# SCH_business-card_2024-06-18.net
KiCad netlist of a schematic drawn in EasyEDA
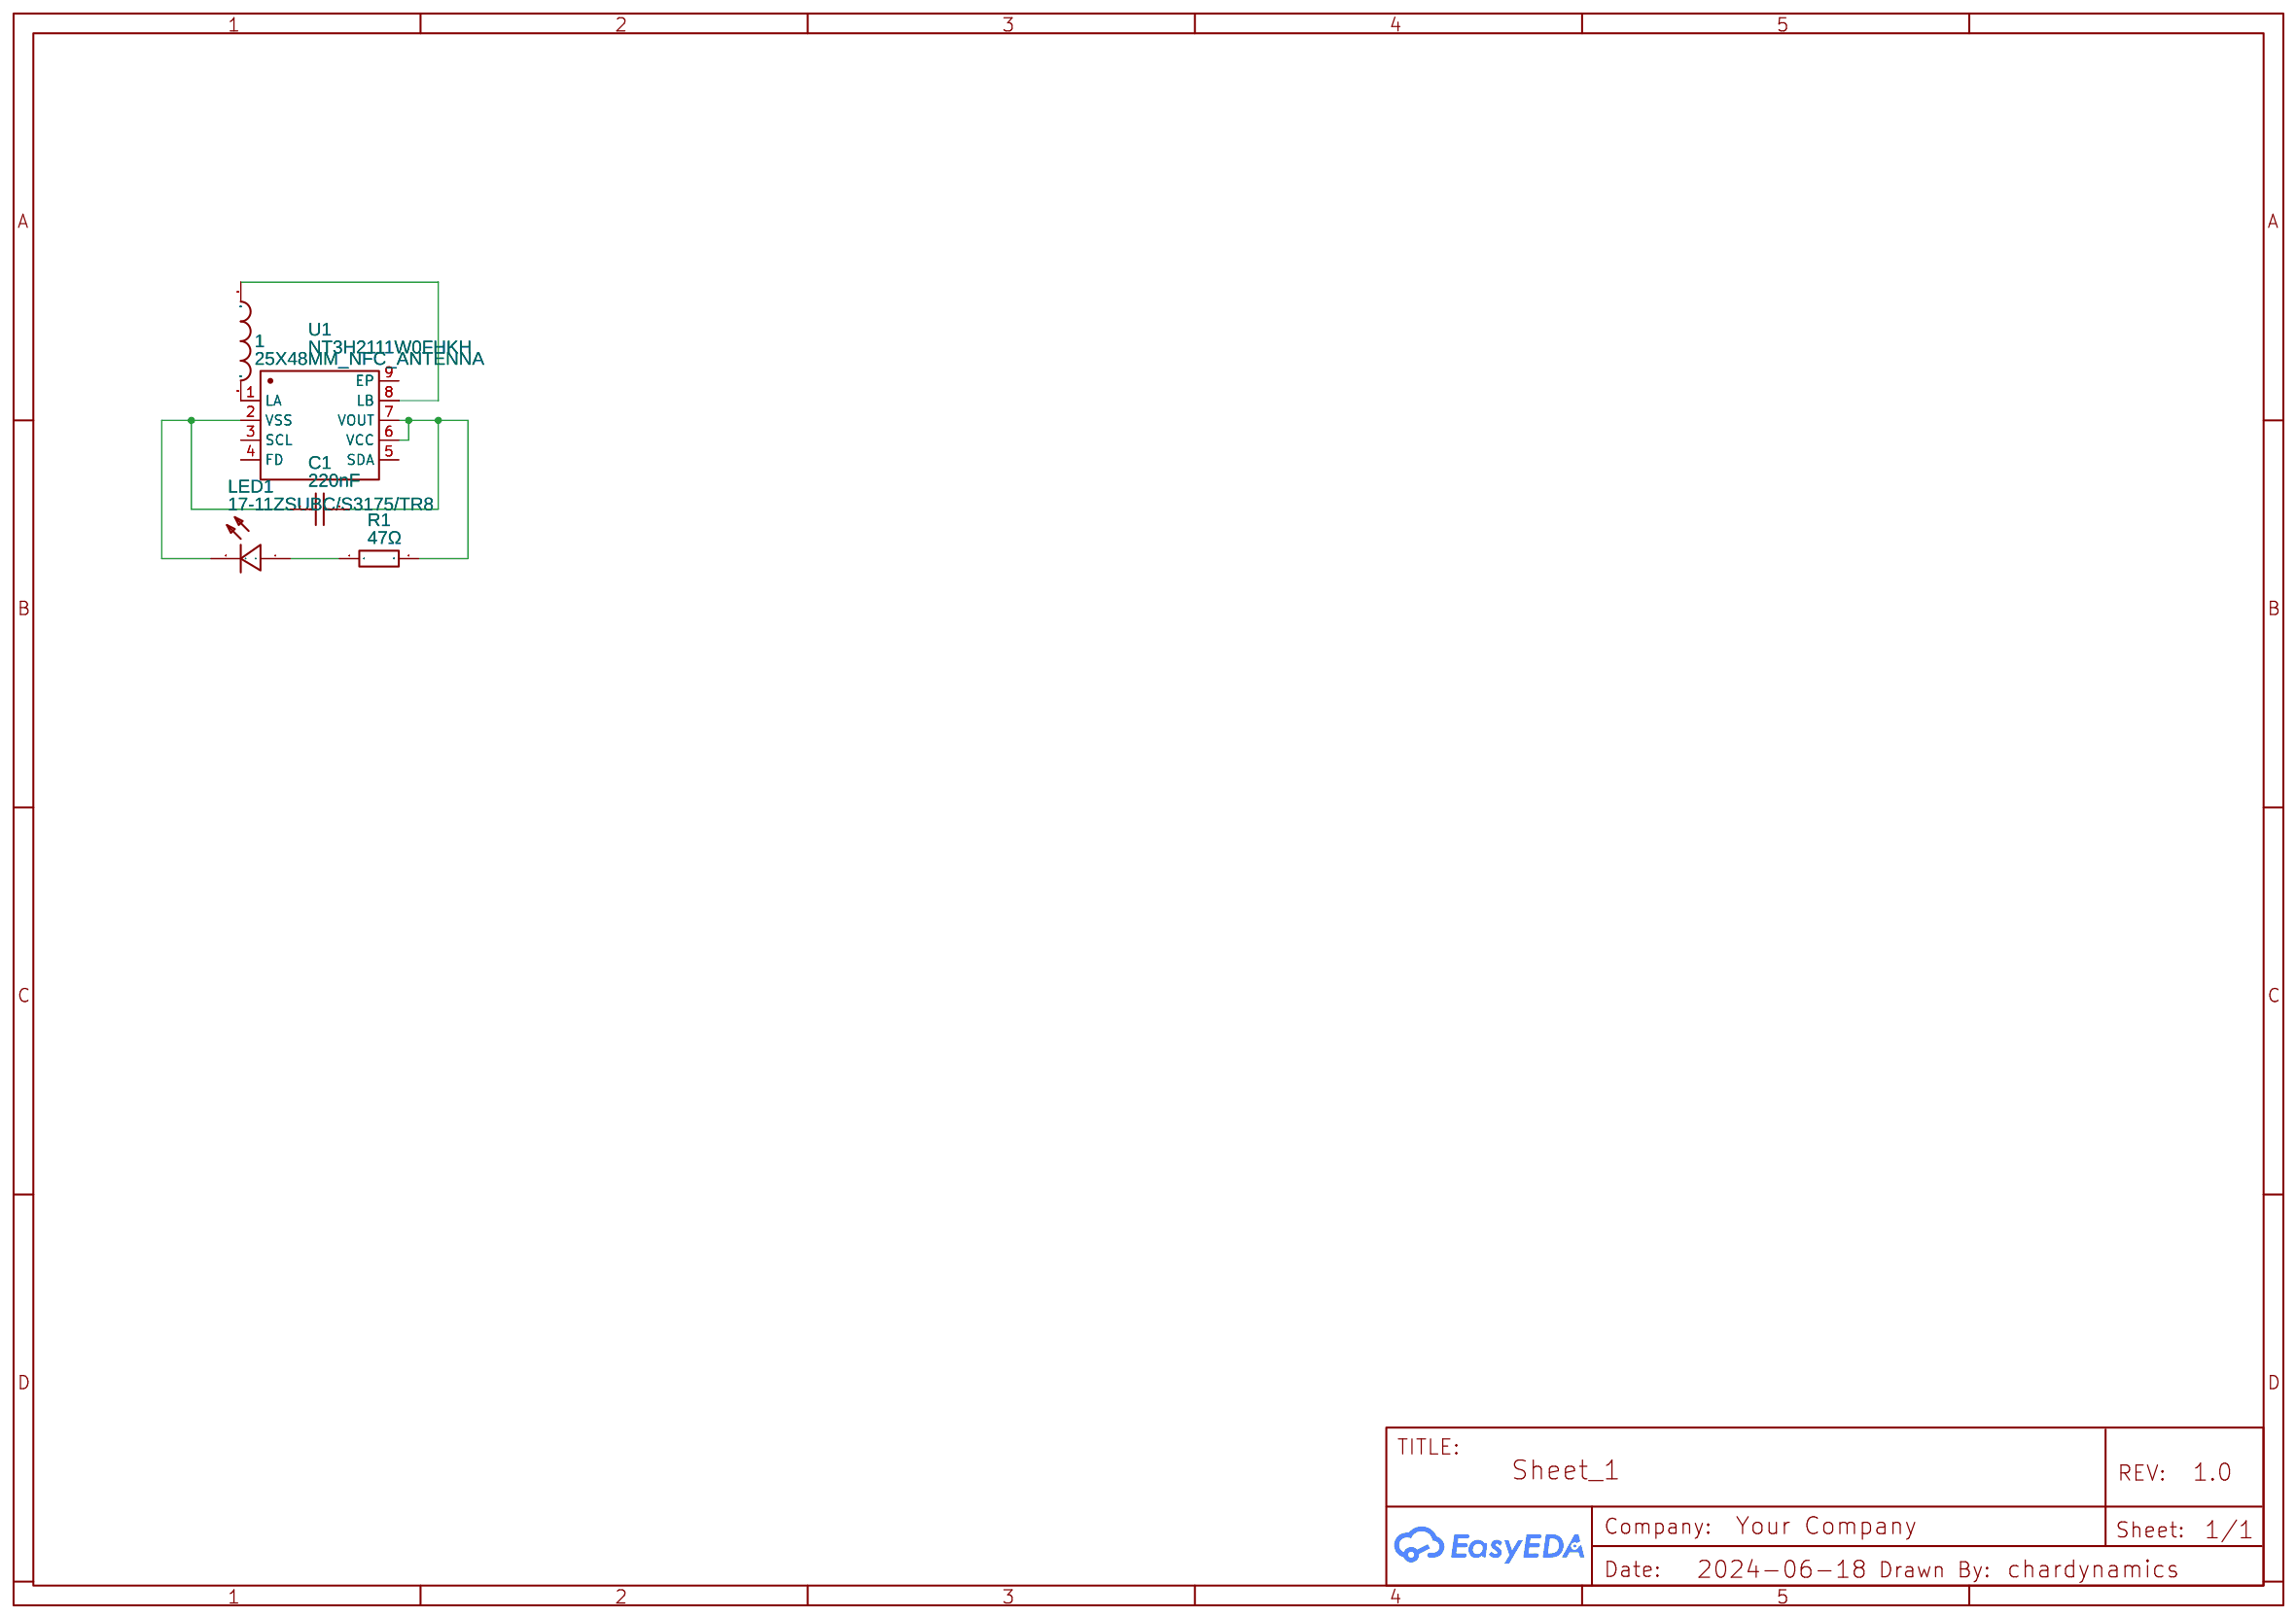
[diagram p0: schematic sheet]

(export (version "E")
  (design (tool "Eeschema 10.0.6"))
  (components
    (comp (ref "1") (value "25X48MM_NFC_ANTENNA") (libsource (lib "") (part "25X48MM_NFC_ANTENNA")))
    (comp (ref "C1")
      (value "220nF")
      (fields
        (field (name "Manufacturer Part") "CL10B224KA8NNNC")
        (field (name "Manufacturer") "SAMSUNG(三星)")
      )
      (libsource (lib "") (part "CL10B224KA8NNNC"))
    )
    (comp (ref "LED1")
      (value "17-11ZSUBC/S3175/TR8")
      (fields (field (name "Manufacturer") "EVERLIGHT(亿光)"))
      (libsource (lib "") (part "17-11ZSUBC/S3175/TR8"))
    )
    (comp (ref "R1")
      (value "47Ω")
      (fields
        (field (name "Manufacturer Part") "0603WAF470JT5E")
        (field (name "Manufacturer") "UNI-ROYAL(厚声)")
      )
      (libsource (lib "") (part "0603WAF470JT5E"))
    )
    (comp (ref "U1")
      (value "NT3H2111W0FHKH")
      (fields (field (name "Manufacturer") "NXP(恩智浦)"))
      (libsource (lib "") (part "NT3H2111W0FHKH"))
    )
  )
  (nets
    (net (code "1") (name "Net-(LED1-A)") (class "Default")
      (node (ref "LED1") (pin "1") (pinfunction "A_1") (pintype "unspecified"))
      (node (ref "R1") (pin "1") (pinfunction "1_1") (pintype "input"))
    )
    (net (code "2") (name "Net-(LED1-K)") (class "Default")
      (node (ref "C1") (pin "1") (pinfunction "1_1") (pintype "input"))
      (node (ref "LED1") (pin "2") (pinfunction "K_2") (pintype "unspecified"))
      (node (ref "U1") (pin "2") (pinfunction "VSS_2") (pintype "unspecified"))
    )
    (net (code "3") (name "Net-(U1-LA)") (class "Default")
      (node (ref "1") (pin "P$2") (pinfunction "P$2_P$2") (pintype "bidirectional"))
      (node (ref "U1") (pin "1") (pinfunction "LA_1") (pintype "unspecified"))
    )
    (net (code "4") (name "Net-(U1-LB)") (class "Default")
      (node (ref "1") (pin "P$1") (pinfunction "P$1_P$1") (pintype "bidirectional"))
      (node (ref "U1") (pin "8") (pinfunction "LB_8") (pintype "unspecified"))
    )
    (net (code "5") (name "Net-(U1-VCC)") (class "Default")
      (node (ref "C1") (pin "2") (pinfunction "2_2") (pintype "input"))
      (node (ref "R1") (pin "2") (pinfunction "2_2") (pintype "input"))
      (node (ref "U1") (pin "6") (pinfunction "VCC_6") (pintype "unspecified"))
      (node (ref "U1") (pin "7") (pinfunction "VOUT_7") (pintype "unspecified"))
    )
    (net (code "6") (name "unconnected-(U1-EP-Pad9)") (class "Default")
      (node (ref "U1") (pin "9") (pinfunction "EP_9") (pintype "unspecified"))
    )
    (net (code "7") (name "unconnected-(U1-FD-Pad4)") (class "Default")
      (node (ref "U1") (pin "4") (pinfunction "FD_4") (pintype "unspecified"))
    )
    (net (code "8") (name "unconnected-(U1-SCL-Pad3)") (class "Default")
      (node (ref "U1") (pin "3") (pinfunction "SCL_3") (pintype "unspecified"))
    )
    (net (code "9") (name "unconnected-(U1-SDA-Pad5)") (class "Default")
      (node (ref "U1") (pin "5") (pinfunction "SDA_5") (pintype "unspecified"))
    )
  )
)
